# lab3_kozlov_motherboard.net
KiCad netlist of a schematic drawn in Altium Designer
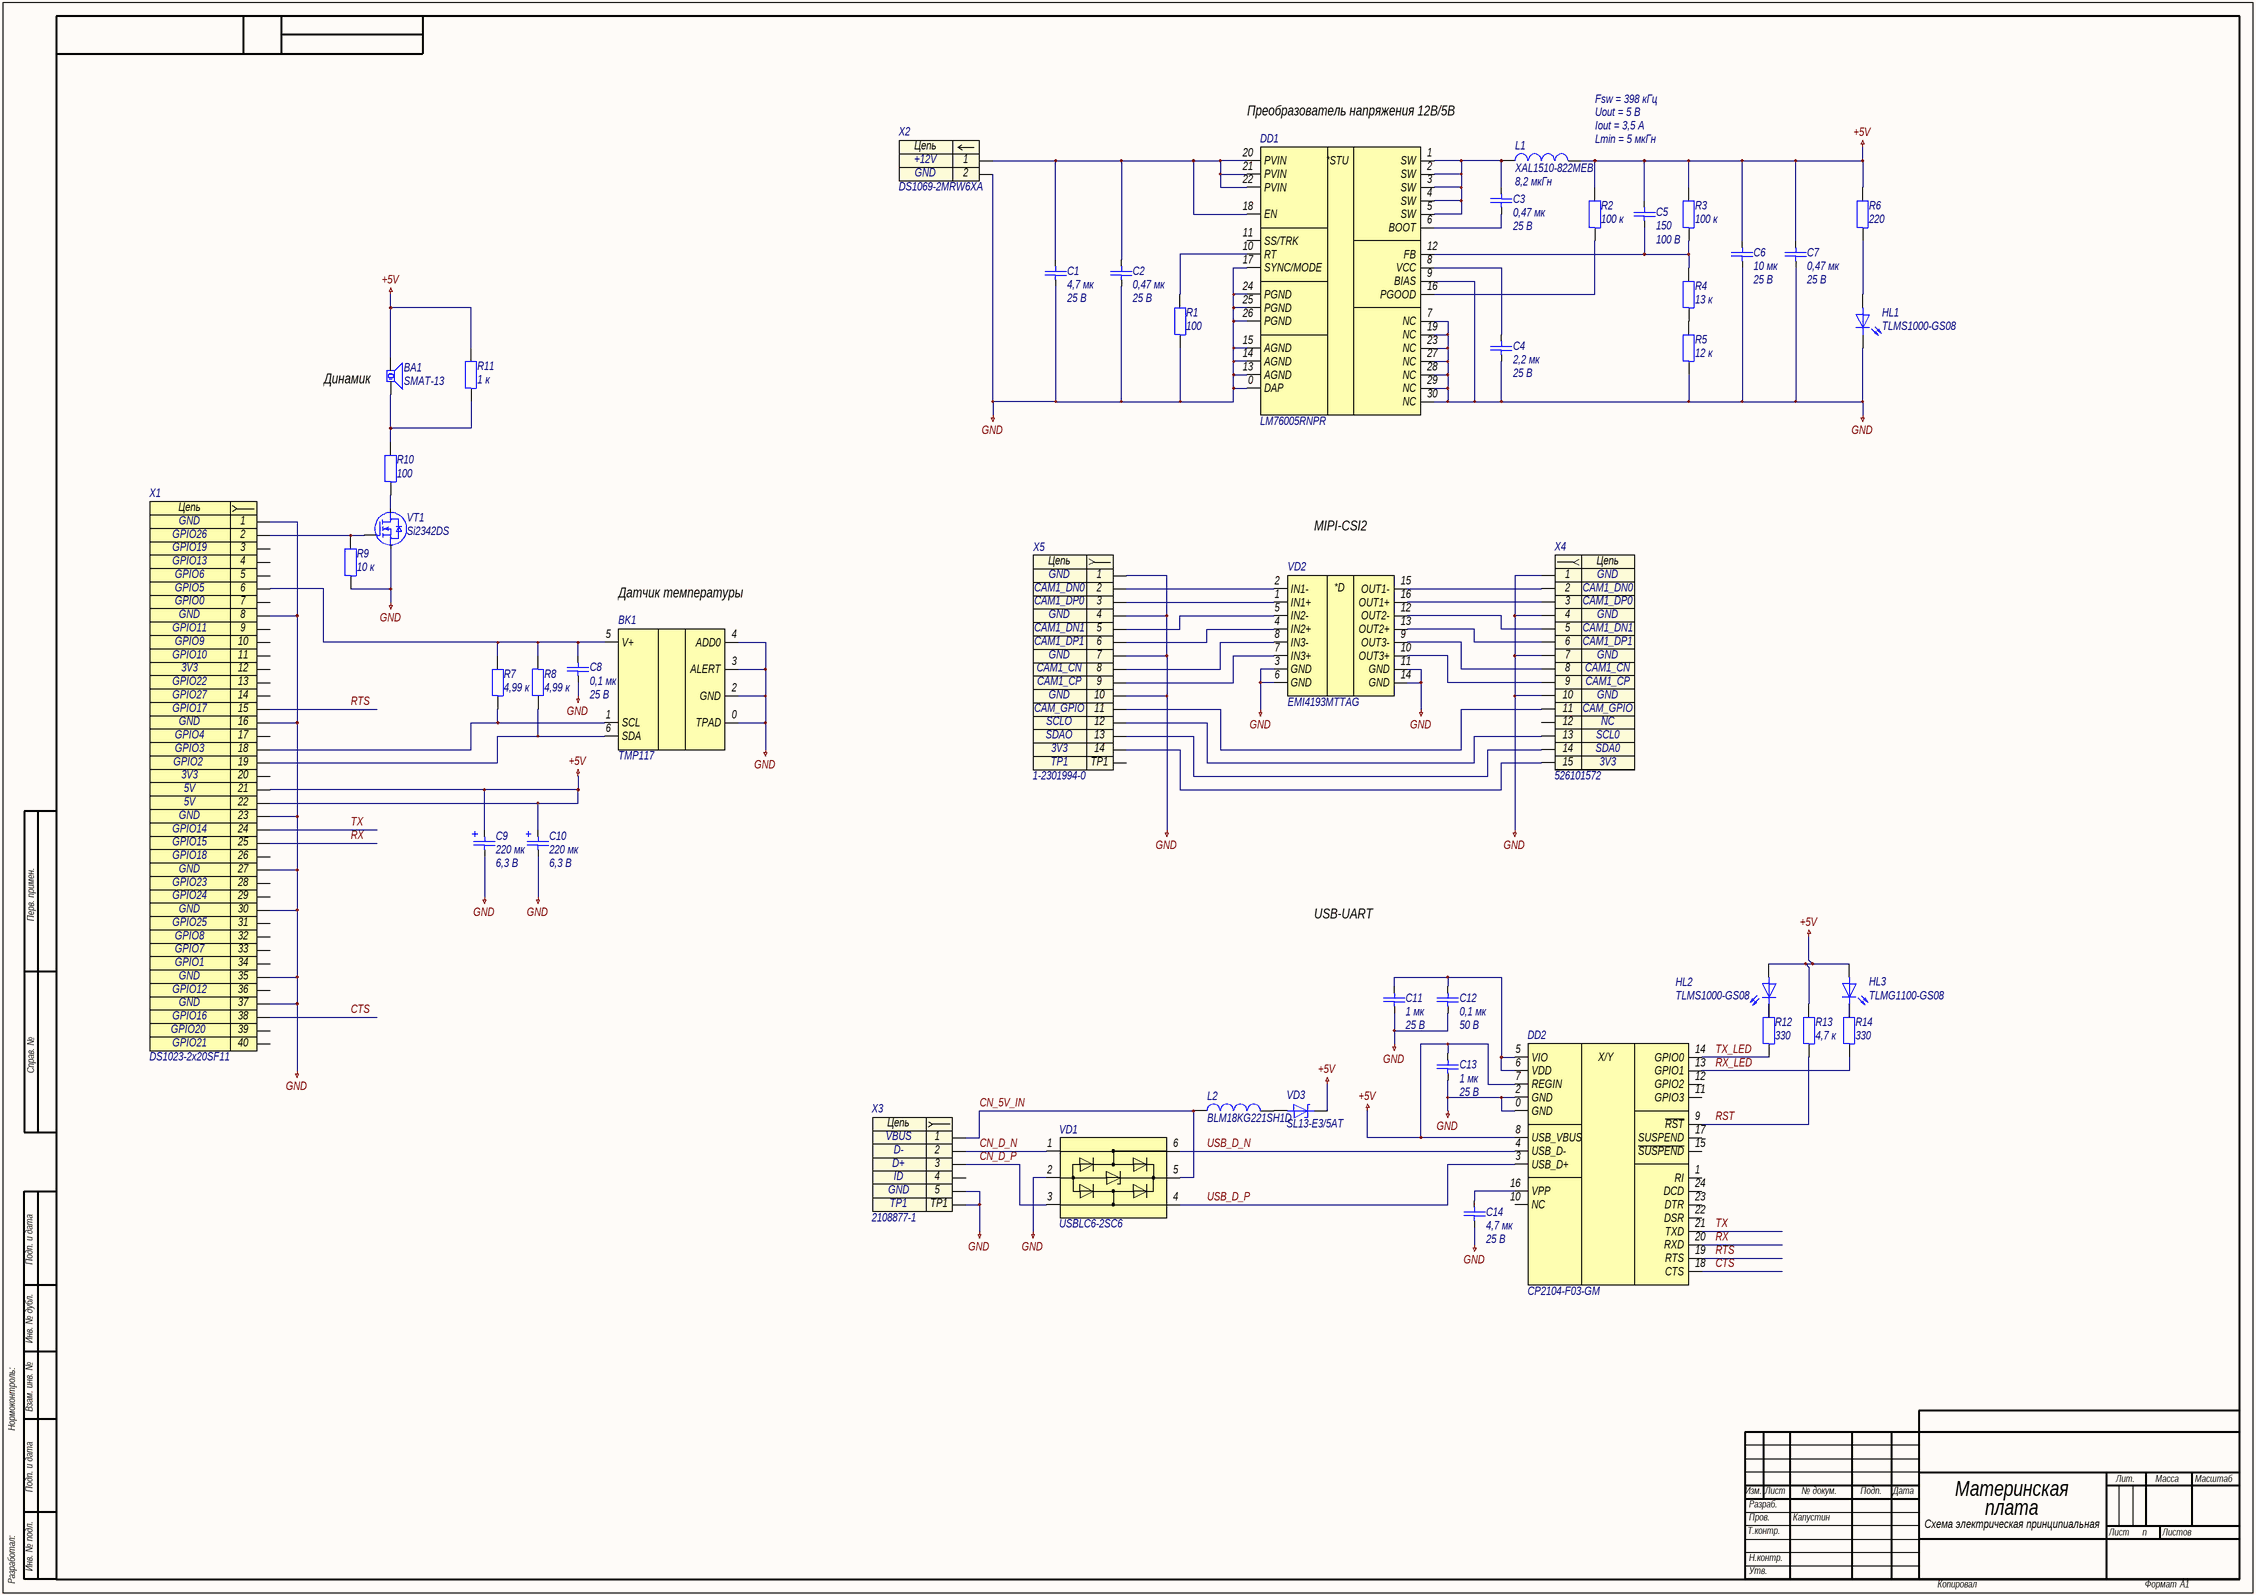
[diagram p0: lab3_kozlov_motherboard.SchDoc]

(export (version "E")
  (design (tool "Eeschema 10.0.6"))
  (components
    (comp (ref "BA1")
      (value "SMAT-13")
      (footprint "SMAT_13")
      (description "https://www.sonitron.be/products/sma-smat-series/")
      (libsource (lib "piezo_sounder") (part "PIEZO_SOUNDER"))
    )
    (comp (ref "BK1")
      (value "TMP117")
      (footprint "TMP117")
      (description "https://www.ti.com/product/TMP117#design-development##hardware-development")
      (libsource (lib "tmp117") (part "TMP117"))
    )
    (comp (ref "C1")
      (value "4,7 мк")
      (footprint "C0805")
      (description "=Описание")
      (fields (field (name "НАПРЯЖЕНИЕ") "25 В"))
      (libsource (lib "Database_Students") (part "CAPACITOR-NONPOLAR"))
    )
    (comp (ref "C2")
      (value "0,47 мк")
      (footprint "C0603")
      (description "=Описание")
      (fields (field (name "НАПРЯЖЕНИЕ") "25 В"))
      (libsource (lib "Database_Students") (part "CAPACITOR-NONPOLAR"))
    )
    (comp (ref "C3")
      (value "0,47 мк")
      (footprint "C0603")
      (description "=Описание")
      (fields (field (name "НАПРЯЖЕНИЕ") "25 В"))
      (libsource (lib "Database_Students") (part "CAPACITOR-NONPOLAR"))
    )
    (comp (ref "C4")
      (value "2,2 мк")
      (footprint "C0805")
      (description "=Описание")
      (fields (field (name "НАПРЯЖЕНИЕ") "25 В"))
      (libsource (lib "Database_Students") (part "CAPACITOR-NONPOLAR"))
    )
    (comp (ref "C5")
      (value "150")
      (footprint "C0805")
      (description "=Описание")
      (fields (field (name "НАПРЯЖЕНИЕ") "100 В"))
      (libsource (lib "Database_Students") (part "CAPACITOR-NONPOLAR"))
    )
    (comp (ref "C6")
      (value "10 мк")
      (footprint "C1206")
      (description "=Описание")
      (fields (field (name "НАПРЯЖЕНИЕ") "25 В"))
      (libsource (lib "Database_Students") (part "CAPACITOR-NONPOLAR"))
    )
    (comp (ref "C7")
      (value "0,47 мк")
      (footprint "C0603")
      (description "=Описание")
      (fields (field (name "НАПРЯЖЕНИЕ") "25 В"))
      (libsource (lib "Database_Students") (part "CAPACITOR-NONPOLAR"))
    )
    (comp (ref "C8")
      (value "0,1 мк")
      (footprint "C0402")
      (description "=Описание")
      (fields (field (name "НАПРЯЖЕНИЕ") "25 В"))
      (libsource (lib "Database_Students") (part "CAPACITOR-NONPOLAR"))
    )
    (comp (ref "C9")
      (value "220 мк")
      (footprint "C7343-43")
      (description "=Описание")
      (fields (field (name "НАПРЯЖЕНИЕ") "6,3 В"))
      (libsource (lib "Database_Students") (part "CAPACITOR-POLAR"))
    )
    (comp (ref "C10")
      (value "220 мк")
      (footprint "C7343-43")
      (description "=Описание")
      (fields (field (name "НАПРЯЖЕНИЕ") "6,3 В"))
      (libsource (lib "Database_Students") (part "CAPACITOR-POLAR"))
    )
    (comp (ref "C11")
      (value "1 мк")
      (footprint "C0603")
      (description "=Описание")
      (fields (field (name "НАПРЯЖЕНИЕ") "25 В"))
      (libsource (lib "Database_Students") (part "CAPACITOR-NONPOLAR"))
    )
    (comp (ref "C12")
      (value "0,1 мк")
      (footprint "C0603")
      (description "=Описание")
      (fields (field (name "НАПРЯЖЕНИЕ") "50 В"))
      (libsource (lib "Database_Students") (part "CAPACITOR-NONPOLAR"))
    )
    (comp (ref "C13")
      (value "1 мк")
      (footprint "C0603")
      (description "=Описание")
      (fields (field (name "НАПРЯЖЕНИЕ") "25 В"))
      (libsource (lib "Database_Students") (part "CAPACITOR-NONPOLAR"))
    )
    (comp (ref "C14")
      (value "4,7 мк")
      (footprint "C0603")
      (description "=Описание")
      (fields (field (name "НАПРЯЖЕНИЕ") "25 В"))
      (libsource (lib "Database_Students") (part "CAPACITOR-NONPOLAR"))
    )
    (comp (ref "DD1")
      (value "LM76005RNPR")
      (footprint "WQFN-30-P50-600X400X80-L55X25-T460X220")
      (description "=Описание")
      (libsource (lib "Database_Students") (part "LM76005RNPR"))
    )
    (comp (ref "DD2")
      (value "CP2104-F03-GM")
      (footprint "QFN-24-P50-400X400X80-L40X25-T270X270")
      (description "=Описание")
      (libsource (lib "Database_Students") (part "CP2104-F03-GM"))
    )
    (comp (ref "HL1")
      (value "TLMS1000-GS08")
      (footprint "HL0603")
      (description "=Описание")
      (libsource (lib "Database_Students") (part "HL-COMMON"))
    )
    (comp (ref "HL2")
      (value "TLMS1000-GS08")
      (footprint "HL0603")
      (description "=Описание")
      (libsource (lib "Database_Students") (part "HL-COMMON"))
    )
    (comp (ref "HL3")
      (value "TLMG1100-GS08")
      (footprint "HL0603")
      (description "=Описание")
      (libsource (lib "Database_Students") (part "HL-COMMON"))
    )
    (comp (ref "L1")
      (value "XAL1510-822MEB")
      (footprint "XAL-2-1620X1520X1000")
      (description "=Описание")
      (fields (field (name "ИНДУКТИВНОСТЬ") "8,2 мкГн"))
      (libsource (lib "Database_Students") (part "INDUCTOR-COMMON"))
    )
    (comp (ref "L2")
      (value "BLM18KG221SH1D")
      (footprint "BLM-2-0603")
      (description "=Описание")
      (libsource (lib "Database_Students") (part "FERRITE-BEAD"))
    )
    (comp (ref "R1")
      (value "100")
      (footprint "R0603")
      (description "=Описание")
      (libsource (lib "Database_Students") (part "RESISTOR-COMMON"))
    )
    (comp (ref "R2")
      (value "100 к")
      (footprint "R0603")
      (description "=Описание")
      (libsource (lib "Database_Students") (part "R-COMMON"))
    )
    (comp (ref "R3")
      (value "100 к")
      (footprint "R0603")
      (description "=Описание")
      (libsource (lib "Database_Students") (part "R-COMMON"))
    )
    (comp (ref "R4")
      (value "13 к")
      (footprint "R0603")
      (description "=Описание")
      (libsource (lib "Database_Students") (part "R-COMMON"))
    )
    (comp (ref "R5")
      (value "12 к")
      (footprint "R0603")
      (description "=Описание")
      (libsource (lib "Database_Students") (part "R-COMMON"))
    )
    (comp (ref "R6")
      (value "220")
      (footprint "R0603")
      (description "=Описание")
      (libsource (lib "Database_Students") (part "R-COMMON"))
    )
    (comp (ref "R7")
      (value "4,99 к")
      (footprint "R0603")
      (description "=Описание")
      (libsource (lib "Database_Students") (part "RESISTOR-COMMON"))
    )
    (comp (ref "R8")
      (value "4,99 к")
      (footprint "R0603")
      (description "=Описание")
      (libsource (lib "Database_Students") (part "RESISTOR-COMMON"))
    )
    (comp (ref "R9")
      (value "10 к")
      (footprint "R0603")
      (description "=Описание")
      (libsource (lib "Database_Students") (part "RESISTOR-COMMON"))
    )
    (comp (ref "R10")
      (value "100")
      (footprint "R0603")
      (description "=Описание")
      (libsource (lib "Database_Students") (part "RESISTOR-COMMON"))
    )
    (comp (ref "R11")
      (value "1 к")
      (footprint "R0603")
      (description "=Описание")
      (libsource (lib "Database_Students") (part "RESISTOR-COMMON"))
    )
    (comp (ref "R12")
      (value "330")
      (footprint "R0603")
      (description "=Описание")
      (libsource (lib "Database_Students") (part "R-COMMON"))
    )
    (comp (ref "R13")
      (value "4,7 к")
      (footprint "R0603")
      (description "=Описание")
      (libsource (lib "Database_Students") (part "R-COMMON"))
    )
    (comp (ref "R14")
      (value "330")
      (footprint "R0603")
      (description "=Описание")
      (libsource (lib "Database_Students") (part "R-COMMON"))
    )
    (comp (ref "VD1")
      (value "USBLC6-2SC6")
      (footprint "SOT-23-6-P95-290X280X145")
      (description "=Описание")
      (libsource (lib "Database_Students") (part "USBLC6-2SC6"))
    )
    (comp (ref "VD2")
      (value "EMI4193MTTAG")
      (footprint "EMI4193")
      (description "https://www.onsemi.com/products/isolation-protection-devices/emi-filters/emi4193")
      (libsource (lib "emi4193") (part "EMI4193"))
    )
    (comp (ref "VD3")
      (value "SL13-E3/5AT")
      (footprint "DO-214AC-510X270X229")
      (description "=Описание")
      (libsource (lib "Database_Students") (part "DIODE-SCHOTTKY"))
    )
    (comp (ref "VT1")
      (value "Si2342DS")
      (footprint "SOT95P237X112-3N")
      (description "=Описание")
      (libsource (lib "Database_Students") (part "MOSFET-N-DIODE"))
    )
    (comp (ref "X1")
      (value "DS1023-2x20SF11")
      (footprint "DS1023-2X20SF11")
      (description "=Описание")
      (libsource (lib "Database_Students") (part "HEADER-40-SCT"))
    )
    (comp (ref "X2")
      (value "DS1069-2MRW6XA")
      (footprint "DS1069-2MRW6XA")
      (description "=Описание")
      (libsource (lib "Database_Students") (part "HEADER-2-PLG"))
    )
    (comp (ref "X3")
      (value "2108877-1")
      (footprint "2108877-1")
      (libsource (lib "Database_Students") (part "HEADER-5-TP1-SCT"))
    )
    (comp (ref "X4")
      (value "526101572")
      (footprint "526101572")
      (description "https://www.molex.com/molex/products/part-detail/ffc_fpc_connectors/0526101572")
      (libsource (lib "526101572") (part "526101572"))
    )
    (comp (ref "X5")
      (value "1-2301994-0")
      (footprint "1-2301994-0")
      (description "=Описание")
      (libsource (lib "Database_Students") (part "HEADER-14-TP1-SCT"))
    )
  )
  (nets
    (net (code "1") (name "+5V") (class "Default")
      (node (ref "BA1") (pin "1") (pinfunction "1_1") (pintype "passive"))
      (node (ref "C10") (pin "1") (pinfunction "1_1") (pintype "passive"))
      (node (ref "C13") (pin "1") (pinfunction "1_1") (pintype "passive"))
      (node (ref "C5") (pin "1") (pinfunction "1_1") (pintype "passive"))
      (node (ref "C6") (pin "1") (pinfunction "1_1") (pintype "passive"))
      (node (ref "C7") (pin "1") (pinfunction "1_1") (pintype "passive"))
      (node (ref "C9") (pin "1") (pinfunction "1_1") (pintype "passive"))
      (node (ref "DD2") (pin "7") (pinfunction "REGIN_7") (pintype "passive"))
      (node (ref "DD2") (pin "8") (pinfunction "USB_VBUS_8") (pintype "passive"))
      (node (ref "HL2") (pin "2") (pinfunction "2_2") (pintype "passive"))
      (node (ref "HL3") (pin "2") (pinfunction "2_2") (pintype "passive"))
      (node (ref "L1") (pin "2") (pinfunction "2_2") (pintype "passive"))
      (node (ref "R11") (pin "2") (pinfunction "2_2") (pintype "passive"))
      (node (ref "R13") (pin "2") (pinfunction "2_2") (pintype "passive"))
      (node (ref "R2") (pin "2") (pinfunction "2_2") (pintype "passive"))
      (node (ref "R3") (pin "2") (pinfunction "2_2") (pintype "passive"))
      (node (ref "R6") (pin "2") (pinfunction "2_2") (pintype "passive"))
      (node (ref "VD3") (pin "1") (pinfunction "1_1") (pintype "passive"))
      (node (ref "X1") (pin "21") (pinfunction "21_21") (pintype "passive"))
      (node (ref "X1") (pin "22") (pinfunction "22_22") (pintype "passive"))
    )
    (net (code "2") (name "/CN_5V_IN") (class "Default")
      (node (ref "L2") (pin "1") (pinfunction "1_1") (pintype "passive"))
      (node (ref "VD1") (pin "5") (pinfunction "5_5") (pintype "passive"))
      (node (ref "X3") (pin "1") (pinfunction "1_1") (pintype "passive"))
    )
    (net (code "3") (name "/CN_D_N") (class "Default")
      (node (ref "VD1") (pin "1") (pinfunction "1_1") (pintype "passive"))
      (node (ref "X3") (pin "2") (pinfunction "2_2") (pintype "passive"))
    )
    (net (code "4") (name "/CN_D_P") (class "Default")
      (node (ref "VD1") (pin "3") (pinfunction "3_3") (pintype "passive"))
      (node (ref "X3") (pin "3") (pinfunction "3_3") (pintype "passive"))
    )
    (net (code "5") (name "/CTS") (class "Default")
      (node (ref "DD2") (pin "18") (pinfunction "CTS_18") (pintype "passive"))
      (node (ref "X1") (pin "38") (pinfunction "38_38") (pintype "passive"))
    )
    (net (code "6") (name "/RST") (class "Default")
      (node (ref "DD2") (pin "9") (pinfunction "~{RST}_9") (pintype "passive"))
      (node (ref "R13") (pin "1") (pinfunction "1_1") (pintype "passive"))
    )
    (net (code "7") (name "/RTS") (class "Default")
      (node (ref "DD2") (pin "19") (pinfunction "RTS_19") (pintype "passive"))
      (node (ref "X1") (pin "15") (pinfunction "15_15") (pintype "passive"))
    )
    (net (code "8") (name "/RX") (class "Default")
      (node (ref "DD2") (pin "20") (pinfunction "RXD_20") (pintype "passive"))
      (node (ref "X1") (pin "25") (pinfunction "25_25") (pintype "passive"))
    )
    (net (code "9") (name "/RX_LED") (class "Default")
      (node (ref "DD2") (pin "13") (pinfunction "GPIO1_13") (pintype "passive"))
      (node (ref "R14") (pin "1") (pinfunction "1_1") (pintype "passive"))
    )
    (net (code "10") (name "/TX") (class "Default")
      (node (ref "DD2") (pin "21") (pinfunction "TXD_21") (pintype "passive"))
      (node (ref "X1") (pin "24") (pinfunction "24_24") (pintype "passive"))
    )
    (net (code "11") (name "/TX_LED") (class "Default")
      (node (ref "DD2") (pin "14") (pinfunction "GPIO0_14") (pintype "passive"))
      (node (ref "R12") (pin "1") (pinfunction "1_1") (pintype "passive"))
    )
    (net (code "12") (name "/USB_D_N") (class "Default")
      (node (ref "DD2") (pin "4") (pinfunction "USB_D-_4") (pintype "passive"))
      (node (ref "VD1") (pin "6") (pinfunction "6_6") (pintype "passive"))
    )
    (net (code "13") (name "/USB_D_P") (class "Default")
      (node (ref "DD2") (pin "3") (pinfunction "USB_D+_3") (pintype "passive"))
      (node (ref "VD1") (pin "4") (pinfunction "4_4") (pintype "passive"))
    )
    (net (code "14") (name "GND") (class "Default")
      (node (ref "BK1") (pin "0") (pinfunction "TPAD_0") (pintype "passive"))
      (node (ref "BK1") (pin "2") (pinfunction "GND_2") (pintype "passive"))
      (node (ref "BK1") (pin "3") (pinfunction "ALERT_3") (pintype "passive"))
      (node (ref "BK1") (pin "4") (pinfunction "ADD0_4") (pintype "passive"))
      (node (ref "C1") (pin "2") (pinfunction "2_2") (pintype "passive"))
      (node (ref "C10") (pin "2") (pinfunction "2_2") (pintype "passive"))
      (node (ref "C11") (pin "2") (pinfunction "2_2") (pintype "passive"))
      (node (ref "C12") (pin "2") (pinfunction "2_2") (pintype "passive"))
      (node (ref "C13") (pin "2") (pinfunction "2_2") (pintype "passive"))
      (node (ref "C14") (pin "2") (pinfunction "2_2") (pintype "passive"))
      (node (ref "C2") (pin "2") (pinfunction "2_2") (pintype "passive"))
      (node (ref "C4") (pin "2") (pinfunction "2_2") (pintype "passive"))
      (node (ref "C6") (pin "2") (pinfunction "2_2") (pintype "passive"))
      (node (ref "C7") (pin "2") (pinfunction "2_2") (pintype "passive"))
      (node (ref "C8") (pin "2") (pinfunction "2_2") (pintype "passive"))
      (node (ref "C9") (pin "2") (pinfunction "2_2") (pintype "passive"))
      (node (ref "DD1") (pin "0") (pinfunction "DAP_0") (pintype "passive"))
      (node (ref "DD1") (pin "13") (pinfunction "AGND_13") (pintype "passive"))
      (node (ref "DD1") (pin "14") (pinfunction "AGND_14") (pintype "passive"))
      (node (ref "DD1") (pin "15") (pinfunction "AGND_15") (pintype "passive"))
      (node (ref "DD1") (pin "17") (pinfunction "SYNC/MODE_17") (pintype "passive"))
      (node (ref "DD1") (pin "19") (pinfunction "NC_19") (pintype "passive"))
      (node (ref "DD1") (pin "23") (pinfunction "NC_23") (pintype "passive"))
      (node (ref "DD1") (pin "24") (pinfunction "PGND_24") (pintype "passive"))
      (node (ref "DD1") (pin "25") (pinfunction "PGND_25") (pintype "passive"))
      (node (ref "DD1") (pin "26") (pinfunction "PGND_26") (pintype "passive"))
      (node (ref "DD1") (pin "27") (pinfunction "NC_27") (pintype "passive"))
      (node (ref "DD1") (pin "28") (pinfunction "NC_28") (pintype "passive"))
      (node (ref "DD1") (pin "29") (pinfunction "NC_29") (pintype "passive"))
      (node (ref "DD1") (pin "30") (pinfunction "NC_30") (pintype "passive"))
      (node (ref "DD1") (pin "7") (pinfunction "NC_7") (pintype "passive"))
      (node (ref "DD1") (pin "9") (pinfunction "BIAS_9") (pintype "passive"))
      (node (ref "DD2") (pin "0") (pinfunction "GND_0") (pintype "passive"))
      (node (ref "DD2") (pin "2") (pinfunction "GND_2") (pintype "passive"))
      (node (ref "HL1") (pin "1") (pinfunction "1_1") (pintype "passive"))
      (node (ref "R1") (pin "1") (pinfunction "1_1") (pintype "passive"))
      (node (ref "R5") (pin "1") (pinfunction "1_1") (pintype "passive"))
      (node (ref "R9") (pin "1") (pinfunction "1_1") (pintype "passive"))
      (node (ref "VD1") (pin "2") (pinfunction "2_2") (pintype "passive"))
      (node (ref "VD2") (pin "11") (pinfunction "GND_11") (pintype "passive"))
      (node (ref "VD2") (pin "14") (pinfunction "GND_14") (pintype "passive"))
      (node (ref "VD2") (pin "3") (pinfunction "GND_3") (pintype "passive"))
      (node (ref "VD2") (pin "6") (pinfunction "GND_6") (pintype "passive"))
      (node (ref "VT1") (pin "S") (pinfunction "S_S") (pintype "passive"))
      (node (ref "X1") (pin "1") (pinfunction "1_1") (pintype "passive"))
      (node (ref "X1") (pin "16") (pinfunction "16_16") (pintype "passive"))
      (node (ref "X1") (pin "23") (pinfunction "23_23") (pintype "passive"))
      (node (ref "X1") (pin "27") (pinfunction "27_27") (pintype "passive"))
      (node (ref "X1") (pin "30") (pinfunction "30_30") (pintype "passive"))
      (node (ref "X1") (pin "35") (pinfunction "35_35") (pintype "passive"))
      (node (ref "X1") (pin "37") (pinfunction "37_37") (pintype "passive"))
      (node (ref "X1") (pin "8") (pinfunction "8_8") (pintype "passive"))
      (node (ref "X2") (pin "2") (pinfunction "2_2") (pintype "passive"))
      (node (ref "X3") (pin "5") (pinfunction "5_5") (pintype "passive"))
      (node (ref "X3") (pin "TP1") (pinfunction "TP1_TP1") (pintype "passive"))
      (node (ref "X4") (pin "1") (pinfunction "1_1") (pintype "passive"))
      (node (ref "X4") (pin "10") (pinfunction "10_10") (pintype "passive"))
      (node (ref "X4") (pin "4") (pinfunction "4_4") (pintype "passive"))
      (node (ref "X4") (pin "7") (pinfunction "7_7") (pintype "passive"))
      (node (ref "X5") (pin "1") (pinfunction "1_1") (pintype "passive"))
      (node (ref "X5") (pin "10") (pinfunction "10_10") (pintype "passive"))
      (node (ref "X5") (pin "4") (pinfunction "4_4") (pintype "passive"))
      (node (ref "X5") (pin "7") (pinfunction "7_7") (pintype "passive"))
    )
    (net (code "15") (name "Net-(BA1-Pad2)") (class "Default")
      (node (ref "BA1") (pin "2") (pinfunction "2_2") (pintype "passive"))
      (node (ref "R10") (pin "2") (pinfunction "2_2") (pintype "passive"))
      (node (ref "R11") (pin "1") (pinfunction "1_1") (pintype "passive"))
    )
    (net (code "16") (name "Net-(BK1-SCL)") (class "Default")
      (node (ref "BK1") (pin "1") (pinfunction "SCL_1") (pintype "passive"))
      (node (ref "R7") (pin "1") (pinfunction "1_1") (pintype "passive"))
      (node (ref "X1") (pin "18") (pinfunction "18_18") (pintype "passive"))
    )
    (net (code "17") (name "Net-(BK1-SDA)") (class "Default")
      (node (ref "BK1") (pin "6") (pinfunction "SDA_6") (pintype "passive"))
      (node (ref "R8") (pin "2") (pinfunction "2_2") (pintype "passive"))
      (node (ref "X1") (pin "19") (pinfunction "19_19") (pintype "passive"))
    )
    (net (code "18") (name "Net-(BK1-V+)") (class "Default")
      (node (ref "BK1") (pin "5") (pinfunction "V+_5") (pintype "passive"))
      (node (ref "C8") (pin "1") (pinfunction "1_1") (pintype "passive"))
      (node (ref "R7") (pin "2") (pinfunction "2_2") (pintype "passive"))
      (node (ref "R8") (pin "1") (pinfunction "1_1") (pintype "passive"))
      (node (ref "X1") (pin "6") (pinfunction "6_6") (pintype "passive"))
    )
    (net (code "19") (name "Net-(C3-Pad2)") (class "Default")
      (node (ref "C3") (pin "2") (pinfunction "2_2") (pintype "passive"))
      (node (ref "DD1") (pin "1") (pinfunction "SW_1") (pintype "passive"))
      (node (ref "DD1") (pin "2") (pinfunction "SW_2") (pintype "passive"))
      (node (ref "DD1") (pin "3") (pinfunction "SW_3") (pintype "passive"))
      (node (ref "DD1") (pin "4") (pinfunction "SW_4") (pintype "passive"))
      (node (ref "DD1") (pin "5") (pinfunction "SW_5") (pintype "passive"))
      (node (ref "L1") (pin "1") (pinfunction "1_1") (pintype "passive"))
    )
    (net (code "20") (name "Net-(DD1-BOOT)") (class "Default")
      (node (ref "C3") (pin "1") (pinfunction "1_1") (pintype "passive"))
      (node (ref "DD1") (pin "6") (pinfunction "BOOT_6") (pintype "passive"))
    )
    (net (code "21") (name "Net-(DD1-EN)") (class "Default")
      (node (ref "C1") (pin "1") (pinfunction "1_1") (pintype "passive"))
      (node (ref "C2") (pin "1") (pinfunction "1_1") (pintype "passive"))
      (node (ref "DD1") (pin "18") (pinfunction "EN_18") (pintype "passive"))
      (node (ref "DD1") (pin "20") (pinfunction "PVIN_20") (pintype "passive"))
      (node (ref "DD1") (pin "21") (pinfunction "PVIN_21") (pintype "passive"))
      (node (ref "DD1") (pin "22") (pinfunction "PVIN_22") (pintype "passive"))
      (node (ref "X2") (pin "1") (pinfunction "1_1") (pintype "passive"))
    )
    (net (code "22") (name "Net-(DD1-FB)") (class "Default")
      (node (ref "C5") (pin "2") (pinfunction "2_2") (pintype "passive"))
      (node (ref "DD1") (pin "12") (pinfunction "FB_12") (pintype "passive"))
      (node (ref "R3") (pin "1") (pinfunction "1_1") (pintype "passive"))
      (node (ref "R4") (pin "2") (pinfunction "2_2") (pintype "passive"))
    )
    (net (code "23") (name "Net-(DD1-PGOOD)") (class "Default")
      (node (ref "DD1") (pin "16") (pinfunction "PGOOD_16") (pintype "passive"))
      (node (ref "R2") (pin "1") (pinfunction "1_1") (pintype "passive"))
    )
    (net (code "24") (name "Net-(DD1-RT)") (class "Default")
      (node (ref "DD1") (pin "10") (pinfunction "RT_10") (pintype "passive"))
      (node (ref "R1") (pin "2") (pinfunction "2_2") (pintype "passive"))
    )
    (net (code "25") (name "Net-(DD1-VCC)") (class "Default")
      (node (ref "C4") (pin "1") (pinfunction "1_1") (pintype "passive"))
      (node (ref "DD1") (pin "8") (pinfunction "VCC_8") (pintype "passive"))
    )
    (net (code "26") (name "Net-(DD2-VDD)") (class "Default")
      (node (ref "C11") (pin "1") (pinfunction "1_1") (pintype "passive"))
      (node (ref "C12") (pin "1") (pinfunction "1_1") (pintype "passive"))
      (node (ref "DD2") (pin "5") (pinfunction "VIO_5") (pintype "passive"))
      (node (ref "DD2") (pin "6") (pinfunction "VDD_6") (pintype "passive"))
    )
    (net (code "27") (name "Net-(DD2-VPP)") (class "Default")
      (node (ref "C14") (pin "1") (pinfunction "1_1") (pintype "passive"))
      (node (ref "DD2") (pin "16") (pinfunction "VPP_16") (pintype "passive"))
    )
    (net (code "28") (name "Net-(HL1-Pad2)") (class "Default")
      (node (ref "HL1") (pin "2") (pinfunction "2_2") (pintype "passive"))
      (node (ref "R6") (pin "1") (pinfunction "1_1") (pintype "passive"))
    )
    (net (code "29") (name "Net-(HL2-Pad1)") (class "Default")
      (node (ref "HL2") (pin "1") (pinfunction "1_1") (pintype "passive"))
      (node (ref "R12") (pin "2") (pinfunction "2_2") (pintype "passive"))
    )
    (net (code "30") (name "Net-(HL3-Pad1)") (class "Default")
      (node (ref "HL3") (pin "1") (pinfunction "1_1") (pintype "passive"))
      (node (ref "R14") (pin "2") (pinfunction "2_2") (pintype "passive"))
    )
    (net (code "31") (name "Net-(L2-Pad2)") (class "Default")
      (node (ref "L2") (pin "2") (pinfunction "2_2") (pintype "passive"))
      (node (ref "VD3") (pin "2") (pinfunction "2_2") (pintype "passive"))
    )
    (net (code "32") (name "Net-(R4-Pad1)") (class "Default")
      (node (ref "R4") (pin "1") (pinfunction "1_1") (pintype "passive"))
      (node (ref "R5") (pin "2") (pinfunction "2_2") (pintype "passive"))
    )
    (net (code "33") (name "Net-(R9-Pad2)") (class "Default")
      (node (ref "R9") (pin "2") (pinfunction "2_2") (pintype "passive"))
      (node (ref "VT1") (pin "G") (pinfunction "G_G") (pintype "passive"))
      (node (ref "X1") (pin "2") (pinfunction "2_2") (pintype "passive"))
    )
    (net (code "34") (name "Net-(R10-Pad1)") (class "Default")
      (node (ref "R10") (pin "1") (pinfunction "1_1") (pintype "passive"))
      (node (ref "VT1") (pin "D") (pinfunction "D_D") (pintype "passive"))
    )
    (net (code "35") (name "Net-(VD2-IN1+)") (class "Default")
      (node (ref "VD2") (pin "1") (pinfunction "IN1+_1") (pintype "passive"))
      (node (ref "X5") (pin "3") (pinfunction "3_3") (pintype "passive"))
    )
    (net (code "36") (name "Net-(VD2-IN1-)") (class "Default")
      (node (ref "VD2") (pin "2") (pinfunction "IN1-_2") (pintype "passive"))
      (node (ref "X5") (pin "2") (pinfunction "2_2") (pintype "passive"))
    )
    (net (code "37") (name "Net-(VD2-IN2+)") (class "Default")
      (node (ref "VD2") (pin "4") (pinfunction "IN2+_4") (pintype "passive"))
      (node (ref "X5") (pin "6") (pinfunction "6_6") (pintype "passive"))
    )
    (net (code "38") (name "Net-(VD2-IN2-)") (class "Default")
      (node (ref "VD2") (pin "5") (pinfunction "IN2-_5") (pintype "passive"))
      (node (ref "X5") (pin "5") (pinfunction "5_5") (pintype "passive"))
    )
    (net (code "39") (name "Net-(VD2-IN3+)") (class "Default")
      (node (ref "VD2") (pin "7") (pinfunction "IN3+_7") (pintype "passive"))
      (node (ref "X5") (pin "9") (pinfunction "9_9") (pintype "passive"))
    )
    (net (code "40") (name "Net-(VD2-IN3-)") (class "Default")
      (node (ref "VD2") (pin "8") (pinfunction "IN3-_8") (pintype "passive"))
      (node (ref "X5") (pin "8") (pinfunction "8_8") (pintype "passive"))
    )
    (net (code "41") (name "Net-(VD2-OUT1+)") (class "Default")
      (node (ref "VD2") (pin "16") (pinfunction "OUT1+_16") (pintype "passive"))
      (node (ref "X4") (pin "3") (pinfunction "3_3") (pintype "passive"))
    )
    (net (code "42") (name "Net-(VD2-OUT1-)") (class "Default")
      (node (ref "VD2") (pin "15") (pinfunction "OUT1-_15") (pintype "passive"))
      (node (ref "X4") (pin "2") (pinfunction "2_2") (pintype "passive"))
    )
    (net (code "43") (name "Net-(VD2-OUT2+)") (class "Default")
      (node (ref "VD2") (pin "13") (pinfunction "OUT2+_13") (pintype "passive"))
      (node (ref "X4") (pin "6") (pinfunction "6_6") (pintype "passive"))
    )
    (net (code "44") (name "Net-(VD2-OUT2-)") (class "Default")
      (node (ref "VD2") (pin "12") (pinfunction "OUT2-_12") (pintype "passive"))
      (node (ref "X4") (pin "5") (pinfunction "5_5") (pintype "passive"))
    )
    (net (code "45") (name "Net-(VD2-OUT3+)") (class "Default")
      (node (ref "VD2") (pin "10") (pinfunction "OUT3+_10") (pintype "passive"))
      (node (ref "X4") (pin "9") (pinfunction "9_9") (pintype "passive"))
    )
    (net (code "46") (name "Net-(VD2-OUT3-)") (class "Default")
      (node (ref "VD2") (pin "9") (pinfunction "OUT3-_9") (pintype "passive"))
      (node (ref "X4") (pin "8") (pinfunction "8_8") (pintype "passive"))
    )
    (net (code "47") (name "Net-(X4-Pad11)") (class "Default")
      (node (ref "X4") (pin "11") (pinfunction "11_11") (pintype "passive"))
      (node (ref "X5") (pin "11") (pinfunction "11_11") (pintype "passive"))
    )
    (net (code "48") (name "Net-(X4-Pad13)") (class "Default")
      (node (ref "X4") (pin "13") (pinfunction "13_13") (pintype "passive"))
      (node (ref "X5") (pin "12") (pinfunction "12_12") (pintype "passive"))
    )
    (net (code "49") (name "Net-(X4-Pad14)") (class "Default")
      (node (ref "X4") (pin "14") (pinfunction "14_14") (pintype "passive"))
      (node (ref "X5") (pin "13") (pinfunction "13_13") (pintype "passive"))
    )
    (net (code "50") (name "Net-(X4-Pad15)") (class "Default")
      (node (ref "X4") (pin "15") (pinfunction "15_15") (pintype "passive"))
      (node (ref "X5") (pin "14") (pinfunction "14_14") (pintype "passive"))
    )
    (net (code "51") (name "unconnected-(DD1-SS{slash}TRK-Pad11)") (class "Default")
      (node (ref "DD1") (pin "11") (pinfunction "SS/TRK_11") (pintype "passive"))
    )
    (net (code "52") (name "unconnected-(DD2-DCD-Pad24)") (class "Default")
      (node (ref "DD2") (pin "24") (pinfunction "DCD_24") (pintype "passive"))
    )
    (net (code "53") (name "unconnected-(DD2-DSR-Pad22)") (class "Default")
      (node (ref "DD2") (pin "22") (pinfunction "DSR_22") (pintype "passive"))
    )
    (net (code "54") (name "unconnected-(DD2-DTR-Pad23)") (class "Default")
      (node (ref "DD2") (pin "23") (pinfunction "DTR_23") (pintype "passive"))
    )
    (net (code "55") (name "unconnected-(DD2-GPIO2-Pad12)") (class "Default")
      (node (ref "DD2") (pin "12") (pinfunction "GPIO2_12") (pintype "passive"))
    )
    (net (code "56") (name "unconnected-(DD2-GPIO3-Pad11)") (class "Default")
      (node (ref "DD2") (pin "11") (pinfunction "GPIO3_11") (pintype "passive"))
    )
    (net (code "57") (name "unconnected-(DD2-NC-Pad10)") (class "Default")
      (node (ref "DD2") (pin "10") (pinfunction "NC_10") (pintype "passive"))
    )
    (net (code "58") (name "unconnected-(DD2-RI-Pad1)") (class "Default")
      (node (ref "DD2") (pin "1") (pinfunction "RI_1") (pintype "passive"))
    )
    (net (code "59") (name "unconnected-(DD2-SUSPEND-Pad17)") (class "Default")
      (node (ref "DD2") (pin "17") (pinfunction "SUSPEND_17") (pintype "passive"))
    )
    (net (code "60") (name "unconnected-(DD2-~{SUSPEND}-Pad15)") (class "Default")
      (node (ref "DD2") (pin "15") (pinfunction "~{SUSPEND}_15") (pintype "passive"))
    )
    (net (code "61") (name "unconnected-(X1-Pad3)") (class "Default")
      (node (ref "X1") (pin "3") (pinfunction "3_3") (pintype "passive"))
    )
    (net (code "62") (name "unconnected-(X1-Pad4)") (class "Default")
      (node (ref "X1") (pin "4") (pinfunction "4_4") (pintype "passive"))
    )
    (net (code "63") (name "unconnected-(X1-Pad5)") (class "Default")
      (node (ref "X1") (pin "5") (pinfunction "5_5") (pintype "passive"))
    )
    (net (code "64") (name "unconnected-(X1-Pad7)") (class "Default")
      (node (ref "X1") (pin "7") (pinfunction "7_7") (pintype "passive"))
    )
    (net (code "65") (name "unconnected-(X1-Pad9)") (class "Default")
      (node (ref "X1") (pin "9") (pinfunction "9_9") (pintype "passive"))
    )
    (net (code "66") (name "unconnected-(X1-Pad10)") (class "Default")
      (node (ref "X1") (pin "10") (pinfunction "10_10") (pintype "passive"))
    )
    (net (code "67") (name "unconnected-(X1-Pad11)") (class "Default")
      (node (ref "X1") (pin "11") (pinfunction "11_11") (pintype "passive"))
    )
    (net (code "68") (name "unconnected-(X1-Pad12)") (class "Default")
      (node (ref "X1") (pin "12") (pinfunction "12_12") (pintype "passive"))
    )
    (net (code "69") (name "unconnected-(X1-Pad13)") (class "Default")
      (node (ref "X1") (pin "13") (pinfunction "13_13") (pintype "passive"))
    )
    (net (code "70") (name "unconnected-(X1-Pad14)") (class "Default")
      (node (ref "X1") (pin "14") (pinfunction "14_14") (pintype "passive"))
    )
    (net (code "71") (name "unconnected-(X1-Pad17)") (class "Default")
      (node (ref "X1") (pin "17") (pinfunction "17_17") (pintype "passive"))
    )
    (net (code "72") (name "unconnected-(X1-Pad20)") (class "Default")
      (node (ref "X1") (pin "20") (pinfunction "20_20") (pintype "passive"))
    )
    (net (code "73") (name "unconnected-(X1-Pad26)") (class "Default")
      (node (ref "X1") (pin "26") (pinfunction "26_26") (pintype "passive"))
    )
    (net (code "74") (name "unconnected-(X1-Pad28)") (class "Default")
      (node (ref "X1") (pin "28") (pinfunction "28_28") (pintype "passive"))
    )
    (net (code "75") (name "unconnected-(X1-Pad29)") (class "Default")
      (node (ref "X1") (pin "29") (pinfunction "29_29") (pintype "passive"))
    )
    (net (code "76") (name "unconnected-(X1-Pad31)") (class "Default")
      (node (ref "X1") (pin "31") (pinfunction "31_31") (pintype "passive"))
    )
    (net (code "77") (name "unconnected-(X1-Pad32)") (class "Default")
      (node (ref "X1") (pin "32") (pinfunction "32_32") (pintype "passive"))
    )
    (net (code "78") (name "unconnected-(X1-Pad33)") (class "Default")
      (node (ref "X1") (pin "33") (pinfunction "33_33") (pintype "passive"))
    )
    (net (code "79") (name "unconnected-(X1-Pad34)") (class "Default")
      (node (ref "X1") (pin "34") (pinfunction "34_34") (pintype "passive"))
    )
    (net (code "80") (name "unconnected-(X1-Pad36)") (class "Default")
      (node (ref "X1") (pin "36") (pinfunction "36_36") (pintype "passive"))
    )
    (net (code "81") (name "unconnected-(X1-Pad39)") (class "Default")
      (node (ref "X1") (pin "39") (pinfunction "39_39") (pintype "passive"))
    )
    (net (code "82") (name "unconnected-(X1-Pad40)") (class "Default")
      (node (ref "X1") (pin "40") (pinfunction "40_40") (pintype "passive"))
    )
    (net (code "83") (name "unconnected-(X3-Pad4)") (class "Default")
      (node (ref "X3") (pin "4") (pinfunction "4_4") (pintype "passive"))
    )
    (net (code "84") (name "unconnected-(X4-Pad12)") (class "Default")
      (node (ref "X4") (pin "12") (pinfunction "12_12") (pintype "passive"))
    )
    (net (code "85") (name "unconnected-(X5-PadTP1)") (class "Default")
      (node (ref "X5") (pin "TP1") (pinfunction "TP1_TP1") (pintype "passive"))
    )
  )
)
